# 03_Sensing.net
KiCad netlist of a schematic drawn in Altium Designer
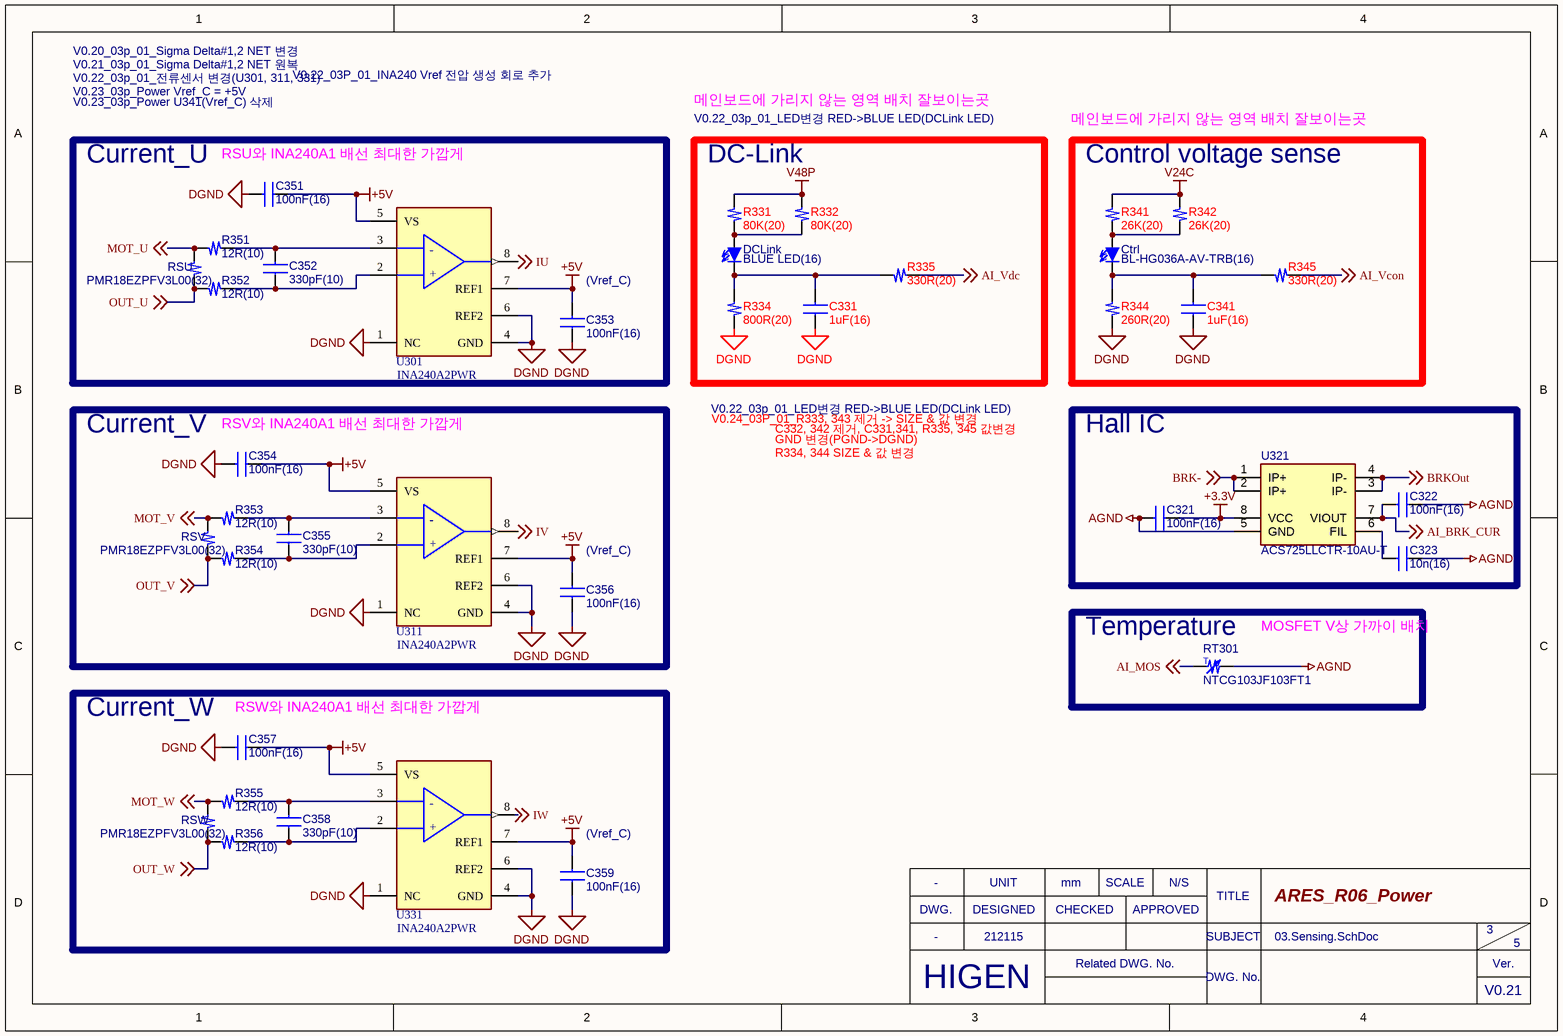
[diagram p0: 03.Sensing.SchDoc]

(export (version "E")
  (design (tool "Eeschema 10.0.6"))
  (components
    (comp (ref "C321") (value "100nF(16)") (footprint "C-1608S") (libsource (lib "HIGEN") (part "RES1")))
    (comp (ref "C322") (value "100nF(16)") (footprint "C-1608S") (libsource (lib "HIGEN") (part "RES1")))
    (comp (ref "C323") (value "10n(16)") (footprint "C-1608S") (libsource (lib "HIGEN") (part "Cap_NP")))
    (comp (ref "C331") (value "1uF(16)") (footprint "C-1608S") (libsource (lib "HIGEN") (part "RES1")))
    (comp (ref "C341") (value "1uF(16)") (footprint "C-1608S") (libsource (lib "HIGEN") (part "RES1")))
    (comp (ref "C351") (value "100nF(16)") (footprint "C-1608S") (libsource (lib "HIGEN") (part "RES1")))
    (comp (ref "C352") (value "330pF(10)") (footprint "C-1005S") (libsource (lib "HIGEN") (part "Cap_NP")))
    (comp (ref "C353") (value "100nF(16)") (footprint "C-1608") (libsource (lib "HIGEN") (part "Cap_NP")))
    (comp (ref "C354") (value "100nF(16)") (footprint "C-1608S") (libsource (lib "HIGEN") (part "RES1")))
    (comp (ref "C355") (value "330pF(10)") (footprint "C-1005S") (libsource (lib "HIGEN") (part "Cap_NP")))
    (comp (ref "C356") (value "100nF(16)") (footprint "C-1608") (libsource (lib "HIGEN") (part "Cap_NP")))
    (comp (ref "C357") (value "100nF(16)") (footprint "C-1608S") (libsource (lib "HIGEN") (part "RES1")))
    (comp (ref "C358") (value "330pF(10)") (footprint "C-1005S") (libsource (lib "HIGEN") (part "Cap_NP")))
    (comp (ref "C359") (value "100nF(16)") (footprint "C-1608") (libsource (lib "HIGEN") (part "Cap_NP")))
    (comp (ref "Ctrl")
      (value "BL-HG036A-AV-TRB(16)")
      (footprint "LED-1608-G")
      (libsource (lib "HIGEN") (part "LED"))
    )
    (comp (ref "DCLink")
      (value "BLUE LED(16)")
      (footprint "LED-1608-B")
      (libsource (lib "HIGEN") (part "LED"))
    )
    (comp (ref "R331") (value "80K(20)") (footprint "R-2012S") (libsource (lib "HIGEN") (part "Res")))
    (comp (ref "R332") (value "80K(20)") (footprint "R-2012S") (libsource (lib "HIGEN") (part "Res")))
    (comp (ref "R334") (value "800R(20)") (footprint "R-2012S") (libsource (lib "HIGEN") (part "Res")))
    (comp (ref "R335") (value "330R(20)") (footprint "R-2012S") (libsource (lib "HIGEN") (part "Res")))
    (comp (ref "R341") (value "26K(20)") (footprint "R-2012S") (libsource (lib "HIGEN") (part "Res")))
    (comp (ref "R342") (value "26K(20)") (footprint "R-2012S") (libsource (lib "HIGEN") (part "Res")))
    (comp (ref "R344") (value "260R(20)") (footprint "R-2012S") (libsource (lib "HIGEN") (part "Res")))
    (comp (ref "R345") (value "330R(20)") (footprint "R-2012S") (libsource (lib "HIGEN") (part "Res")))
    (comp (ref "R351") (value "12R(10)") (footprint "R-1005S") (libsource (lib "HIGEN") (part "Res")))
    (comp (ref "R352") (value "12R(10)") (footprint "R-1005S") (libsource (lib "HIGEN") (part "Res")))
    (comp (ref "R353") (value "12R(10)") (footprint "R-1005S") (libsource (lib "HIGEN") (part "Res")))
    (comp (ref "R354") (value "12R(10)") (footprint "R-1005S") (libsource (lib "HIGEN") (part "Res")))
    (comp (ref "R355") (value "12R(10)") (footprint "R-1005S") (libsource (lib "HIGEN") (part "Res")))
    (comp (ref "R356") (value "12R(10)") (footprint "R-1005S") (libsource (lib "HIGEN") (part "Res")))
    (comp (ref "RSU")
      (value "PMR18EZPFV3L00(32)")
      (footprint "R-3216")
      (libsource (lib "HIGEN") (part "Res"))
    )
    (comp (ref "RSV")
      (value "PMR18EZPFV3L00(32)")
      (footprint "R-3216")
      (libsource (lib "HIGEN") (part "Res"))
    )
    (comp (ref "RSW")
      (value "PMR18EZPFV3L00(32)")
      (footprint "R-3216")
      (libsource (lib "HIGEN") (part "Res"))
    )
    (comp (ref "RT301")
      (value "NTCG103JF103FT1")
      (footprint "L-1005")
      (libsource (lib "HIGEN") (part "Res_Thermal"))
    )
    (comp (ref "U301")
      (value "INA240A2PWR")
      (footprint "TSSOP-8")
      (description "IC CURR SENSE 1 CIRCUIT 8TSSOP")
      (fields
        (field (name "DIGIKEY PART NUMBER") "296-45088-1-ND")
        (field (name "MANUFACTURER") "Texas Instruments")
      )
      (libsource (lib "EEConcierge") (part "INA240A1PWR"))
    )
    (comp (ref "U311")
      (value "INA240A2PWR")
      (footprint "TSSOP-8")
      (description "IC CURR SENSE 1 CIRCUIT 8TSSOP")
      (fields
        (field (name "DIGIKEY PART NUMBER") "296-45088-1-ND")
        (field (name "MANUFACTURER") "Texas Instruments")
      )
      (libsource (lib "EEConcierge") (part "INA240A1PWR"))
    )
    (comp (ref "U321")
      (value "ACS725LLCTR-10AU-T")
      (footprint "SO-8")
      (libsource (lib "HIGEN") (part "ACS725LLCTR"))
    )
    (comp (ref "U331")
      (value "INA240A2PWR")
      (footprint "TSSOP-8")
      (description "IC CURR SENSE 1 CIRCUIT 8TSSOP")
      (fields
        (field (name "DIGIKEY PART NUMBER") "296-45088-1-ND")
        (field (name "MANUFACTURER") "Texas Instruments")
      )
      (libsource (lib "EEConcierge") (part "INA240A1PWR"))
    )
  )
  (nets
    (net (code "1") (name "+3.3V") (class "Default")
      (node (ref "C321") (pin "2") (pinfunction "2_2") (pintype "passive"))
      (node (ref "U321") (pin "8") (pinfunction "VCC_8") (pintype "passive"))
    )
    (net (code "2") (name "+5V") (class "Default")
      (node (ref "C351") (pin "1") (pinfunction "1_1") (pintype "passive"))
      (node (ref "C353") (pin "1") (pinfunction "1_1") (pintype "passive"))
      (node (ref "C354") (pin "1") (pinfunction "1_1") (pintype "passive"))
      (node (ref "C356") (pin "1") (pinfunction "1_1") (pintype "passive"))
      (node (ref "C357") (pin "1") (pinfunction "1_1") (pintype "passive"))
      (node (ref "C359") (pin "1") (pinfunction "1_1") (pintype "passive"))
      (node (ref "U301") (pin "5") (pinfunction "VS_5") (pintype "power_in"))
      (node (ref "U301") (pin "7") (pinfunction "REF1_7") (pintype "passive"))
      (node (ref "U311") (pin "5") (pinfunction "VS_5") (pintype "power_in"))
      (node (ref "U311") (pin "7") (pinfunction "REF1_7") (pintype "passive"))
      (node (ref "U331") (pin "5") (pinfunction "VS_5") (pintype "power_in"))
      (node (ref "U331") (pin "7") (pinfunction "REF1_7") (pintype "passive"))
    )
    (net (code "3") (name "AGND") (class "Default")
      (node (ref "C321") (pin "1") (pinfunction "1_1") (pintype "passive"))
      (node (ref "C322") (pin "2") (pinfunction "2_2") (pintype "passive"))
      (node (ref "C323") (pin "2") (pinfunction "2_2") (pintype "passive"))
      (node (ref "RT301") (pin "1") (pinfunction "1_1") (pintype "passive"))
      (node (ref "U321") (pin "5") (pinfunction "GND_5") (pintype "passive"))
    )
    (net (code "4") (name "AI_BRK_CUR") (class "Default")
      (node (ref "C322") (pin "1") (pinfunction "1_1") (pintype "passive"))
      (node (ref "U321") (pin "7") (pinfunction "VIOUT_7") (pintype "passive"))
    )
    (net (code "5") (name "AI_MOS") (class "Default")
      (node (ref "RT301") (pin "2") (pinfunction "2_2") (pintype "passive"))
    )
    (net (code "6") (name "AI_Vcon") (class "Default")
      (node (ref "R345") (pin "2") (pinfunction "P2_2") (pintype "passive"))
    )
    (net (code "7") (name "AI_Vdc") (class "Default")
      (node (ref "R335") (pin "2") (pinfunction "P2_2") (pintype "passive"))
    )
    (net (code "8") (name "BRK-") (class "Default")
      (node (ref "U321") (pin "1") (pinfunction "IP+_1") (pintype "passive"))
      (node (ref "U321") (pin "2") (pinfunction "IP+_2") (pintype "passive"))
    )
    (net (code "9") (name "BRKOut") (class "Default")
      (node (ref "U321") (pin "3") (pinfunction "IP-_3") (pintype "passive"))
      (node (ref "U321") (pin "4") (pinfunction "IP-_4") (pintype "passive"))
    )
    (net (code "10") (name "DGND") (class "Default")
      (node (ref "C331") (pin "2") (pinfunction "2_2") (pintype "passive"))
      (node (ref "C341") (pin "2") (pinfunction "2_2") (pintype "passive"))
      (node (ref "C351") (pin "2") (pinfunction "2_2") (pintype "passive"))
      (node (ref "C353") (pin "2") (pinfunction "2_2") (pintype "passive"))
      (node (ref "C354") (pin "2") (pinfunction "2_2") (pintype "passive"))
      (node (ref "C356") (pin "2") (pinfunction "2_2") (pintype "passive"))
      (node (ref "C357") (pin "2") (pinfunction "2_2") (pintype "passive"))
      (node (ref "C359") (pin "2") (pinfunction "2_2") (pintype "passive"))
      (node (ref "R334") (pin "2") (pinfunction "P2_2") (pintype "passive"))
      (node (ref "R344") (pin "2") (pinfunction "P2_2") (pintype "passive"))
      (node (ref "U301") (pin "1") (pinfunction "NC_1") (pintype "passive"))
      (node (ref "U301") (pin "4") (pinfunction "GND_4") (pintype "power_in"))
      (node (ref "U301") (pin "6") (pinfunction "REF2_6") (pintype "passive"))
      (node (ref "U311") (pin "1") (pinfunction "NC_1") (pintype "passive"))
      (node (ref "U311") (pin "4") (pinfunction "GND_4") (pintype "power_in"))
      (node (ref "U311") (pin "6") (pinfunction "REF2_6") (pintype "passive"))
      (node (ref "U331") (pin "1") (pinfunction "NC_1") (pintype "passive"))
      (node (ref "U331") (pin "4") (pinfunction "GND_4") (pintype "power_in"))
      (node (ref "U331") (pin "6") (pinfunction "REF2_6") (pintype "passive"))
    )
    (net (code "11") (name "IU") (class "Default")
      (node (ref "U301") (pin "8") (pinfunction "OUT_8") (pintype "output"))
    )
    (net (code "12") (name "IV") (class "Default")
      (node (ref "U311") (pin "8") (pinfunction "OUT_8") (pintype "output"))
    )
    (net (code "13") (name "IW") (class "Default")
      (node (ref "U331") (pin "8") (pinfunction "OUT_8") (pintype "output"))
    )
    (net (code "14") (name "MOT_U") (class "Default")
      (node (ref "R351") (pin "1") (pinfunction "P1_1") (pintype "passive"))
      (node (ref "RSU") (pin "1") (pinfunction "P1_1") (pintype "passive"))
    )
    (net (code "15") (name "MOT_V") (class "Default")
      (node (ref "R353") (pin "1") (pinfunction "P1_1") (pintype "passive"))
      (node (ref "RSV") (pin "1") (pinfunction "P1_1") (pintype "passive"))
    )
    (net (code "16") (name "MOT_W") (class "Default")
      (node (ref "R355") (pin "1") (pinfunction "P1_1") (pintype "passive"))
      (node (ref "RSW") (pin "1") (pinfunction "P1_1") (pintype "passive"))
    )
    (net (code "17") (name "Net-(Ctrl-Anode)") (class "Default")
      (node (ref "Ctrl") (pin "1") (pinfunction "Anode_1") (pintype "passive"))
      (node (ref "R341") (pin "2") (pinfunction "P2_2") (pintype "passive"))
      (node (ref "R342") (pin "2") (pinfunction "P2_2") (pintype "passive"))
    )
    (net (code "18") (name "Net-(Ctrl-Cathode)") (class "Default")
      (node (ref "C341") (pin "1") (pinfunction "1_1") (pintype "passive"))
      (node (ref "Ctrl") (pin "2") (pinfunction "Cathode_2") (pintype "passive"))
      (node (ref "R344") (pin "1") (pinfunction "P1_1") (pintype "passive"))
      (node (ref "R345") (pin "1") (pinfunction "P1_1") (pintype "passive"))
    )
    (net (code "19") (name "Net-(DCLink-Anode)") (class "Default")
      (node (ref "DCLink") (pin "1") (pinfunction "Anode_1") (pintype "passive"))
      (node (ref "R331") (pin "2") (pinfunction "P2_2") (pintype "passive"))
      (node (ref "R332") (pin "2") (pinfunction "P2_2") (pintype "passive"))
    )
    (net (code "20") (name "Net-(DCLink-Cathode)") (class "Default")
      (node (ref "C331") (pin "1") (pinfunction "1_1") (pintype "passive"))
      (node (ref "DCLink") (pin "2") (pinfunction "Cathode_2") (pintype "passive"))
      (node (ref "R334") (pin "1") (pinfunction "P1_1") (pintype "passive"))
      (node (ref "R335") (pin "1") (pinfunction "P1_1") (pintype "passive"))
    )
    (net (code "21") (name "Net-(R351-P2)") (class "Default")
      (node (ref "C352") (pin "2") (pinfunction "2_2") (pintype "passive"))
      (node (ref "R351") (pin "2") (pinfunction "P2_2") (pintype "passive"))
      (node (ref "U301") (pin "3") (pinfunction "IN-_3") (pintype "tri_state"))
    )
    (net (code "22") (name "Net-(R352-P2)") (class "Default")
      (node (ref "C352") (pin "1") (pinfunction "1_1") (pintype "passive"))
      (node (ref "R352") (pin "2") (pinfunction "P2_2") (pintype "passive"))
      (node (ref "U301") (pin "2") (pinfunction "IN+_2") (pintype "tri_state"))
    )
    (net (code "23") (name "Net-(R353-P2)") (class "Default")
      (node (ref "C355") (pin "2") (pinfunction "2_2") (pintype "passive"))
      (node (ref "R353") (pin "2") (pinfunction "P2_2") (pintype "passive"))
      (node (ref "U311") (pin "3") (pinfunction "IN-_3") (pintype "tri_state"))
    )
    (net (code "24") (name "Net-(R354-P2)") (class "Default")
      (node (ref "C355") (pin "1") (pinfunction "1_1") (pintype "passive"))
      (node (ref "R354") (pin "2") (pinfunction "P2_2") (pintype "passive"))
      (node (ref "U311") (pin "2") (pinfunction "IN+_2") (pintype "tri_state"))
    )
    (net (code "25") (name "Net-(R355-P2)") (class "Default")
      (node (ref "C358") (pin "2") (pinfunction "2_2") (pintype "passive"))
      (node (ref "R355") (pin "2") (pinfunction "P2_2") (pintype "passive"))
      (node (ref "U331") (pin "3") (pinfunction "IN-_3") (pintype "tri_state"))
    )
    (net (code "26") (name "Net-(R356-P2)") (class "Default")
      (node (ref "C358") (pin "1") (pinfunction "1_1") (pintype "passive"))
      (node (ref "R356") (pin "2") (pinfunction "P2_2") (pintype "passive"))
      (node (ref "U331") (pin "2") (pinfunction "IN+_2") (pintype "tri_state"))
    )
    (net (code "27") (name "Net-(U321-FIL)") (class "Default")
      (node (ref "C323") (pin "1") (pinfunction "1_1") (pintype "passive"))
      (node (ref "U321") (pin "6") (pinfunction "FIL_6") (pintype "passive"))
    )
    (net (code "28") (name "OUT_U") (class "Default")
      (node (ref "R352") (pin "1") (pinfunction "P1_1") (pintype "passive"))
      (node (ref "RSU") (pin "2") (pinfunction "P2_2") (pintype "passive"))
    )
    (net (code "29") (name "OUT_V") (class "Default")
      (node (ref "R354") (pin "1") (pinfunction "P1_1") (pintype "passive"))
      (node (ref "RSV") (pin "2") (pinfunction "P2_2") (pintype "passive"))
    )
    (net (code "30") (name "OUT_W") (class "Default")
      (node (ref "R356") (pin "1") (pinfunction "P1_1") (pintype "passive"))
      (node (ref "RSW") (pin "2") (pinfunction "P2_2") (pintype "passive"))
    )
    (net (code "31") (name "V24C") (class "Default")
      (node (ref "R341") (pin "1") (pinfunction "P1_1") (pintype "passive"))
      (node (ref "R342") (pin "1") (pinfunction "P1_1") (pintype "passive"))
    )
    (net (code "32") (name "V48P") (class "Default")
      (node (ref "R331") (pin "1") (pinfunction "P1_1") (pintype "passive"))
      (node (ref "R332") (pin "1") (pinfunction "P1_1") (pintype "passive"))
    )
  )
)
